# Tractive_System.net
KiCad netlist of a schematic drawn in EAGLE
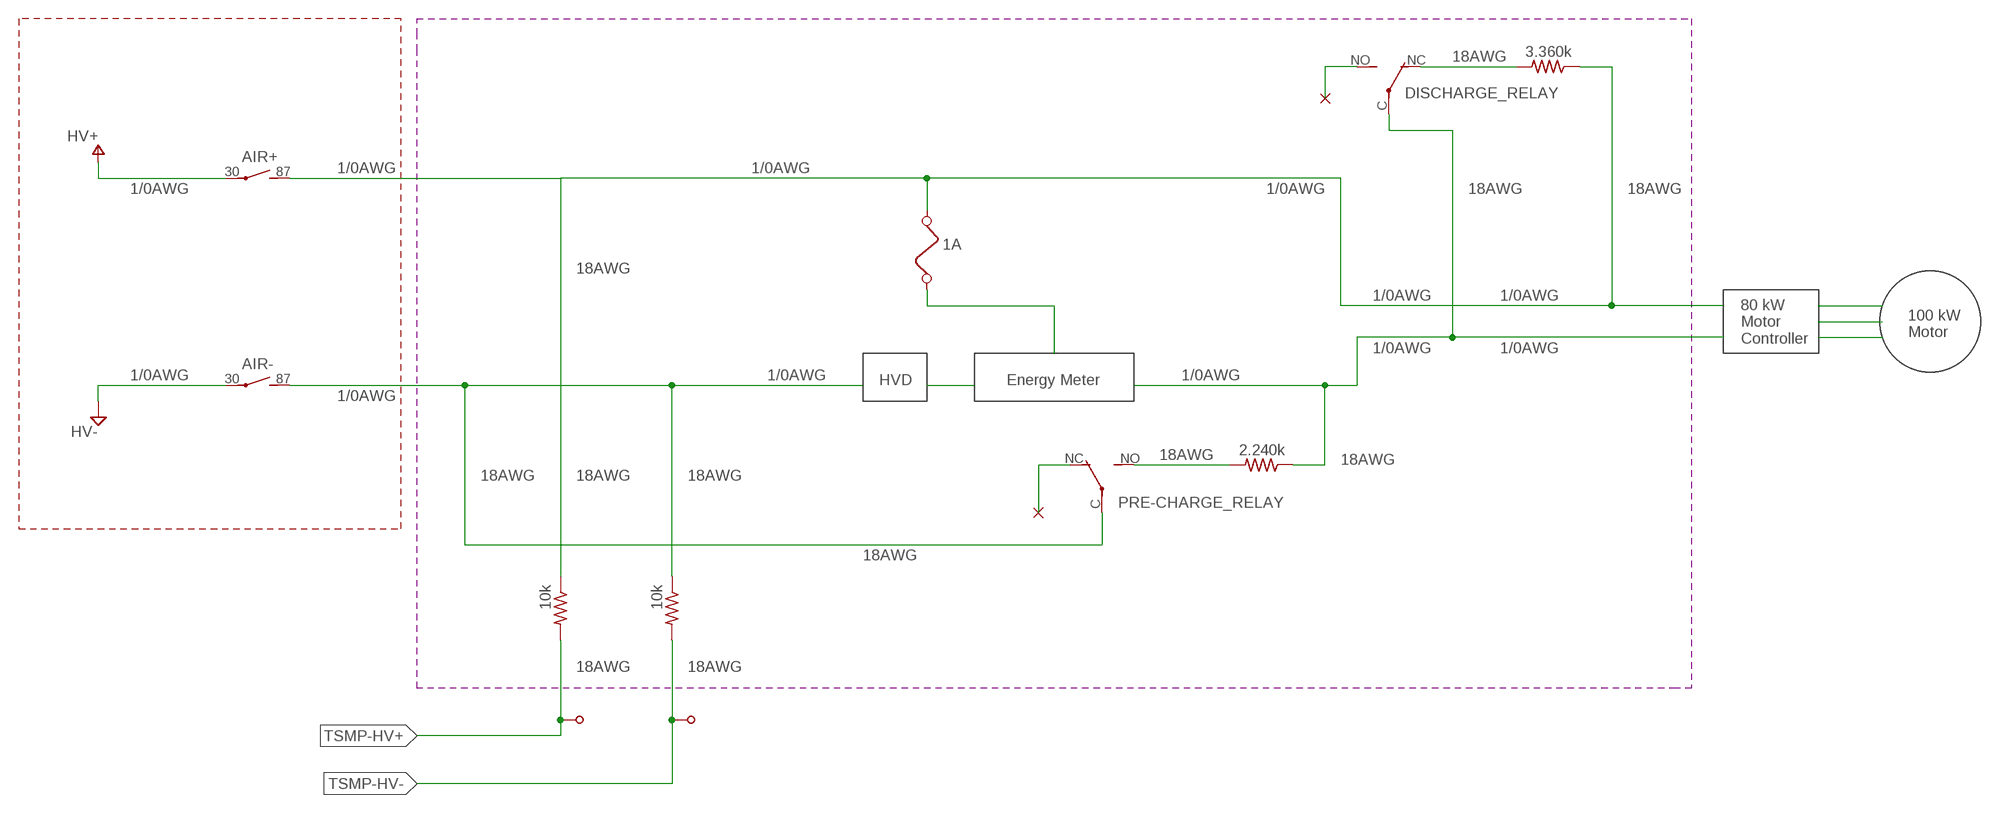
[diagram p0: schematic, sheet 1]

(export (version "E")
  (design (tool "Eeschema 10.0.6"))
  (components
    (comp (ref "AIR+")
      (value "CB1A-P-12V")
      (footprint "eagle-import:CB1")
      (fields (field (name "MF") "AROMAT/ MATSUSHITA"))
      (libsource (lib "eagle-import") (part "CB1A-P-12V"))
    )
    (comp (ref "AIR-")
      (value "CB1A-P-12V")
      (footprint "eagle-import:CB1")
      (fields (field (name "MF") "AROMAT/ MATSUSHITA"))
      (libsource (lib "eagle-import") (part "CB1A-P-12V"))
    )
    (comp (ref "DISCHARGE_RELAY")
      (value "CT112")
      (footprint "eagle-import:CT-SLIM")
      (libsource (lib "eagle-import") (part "CT112"))
    )
    (comp (ref "F1")
      (value "1A")
      (footprint "eagle-import:FUSE")
      (libsource (lib "eagle-import") (part "FUSE"))
    )
    (comp (ref "PRE-CHARGE_RELAY")
      (value "CT112")
      (footprint "eagle-import:CT-SLIM")
      (libsource (lib "eagle-import") (part "CT112"))
    )
    (comp (ref "R1")
      (value "3.360k")
      (footprint "eagle-import:R0805")
      (libsource (lib "eagle-import") (part "R-US_R0805"))
    )
    (comp (ref "R2")
      (value "10k")
      (footprint "eagle-import:R0805")
      (libsource (lib "eagle-import") (part "R-US_R0805"))
    )
    (comp (ref "R3")
      (value "2.240k")
      (footprint "eagle-import:R0805")
      (libsource (lib "eagle-import") (part "R-US_R0805"))
    )
    (comp (ref "R4")
      (value "10k")
      (footprint "eagle-import:R0805")
      (libsource (lib "eagle-import") (part "R-US_R0805"))
    )
    (comp (ref "U$1")
      (value "BANANA-JACK")
      (footprint "eagle-import:BANANA-PRINT")
      (libsource (lib "eagle-import") (part "BANANA-JACK"))
    )
    (comp (ref "U$3")
      (value "BANANA-JACK")
      (footprint "eagle-import:BANANA-PRINT")
      (libsource (lib "eagle-import") (part "BANANA-JACK"))
    )
  )
  (nets
    (net (code "1") (name "HV+") (class "Default")
      (node (ref "AIR+") (pin "30") (pinfunction "P_30") (pintype "passive"))
    )
    (net (code "2") (name "HV-") (class "Default")
      (node (ref "AIR-") (pin "30") (pinfunction "P_30") (pintype "passive"))
    )
    (net (code "3") (name "Net-(AIR+B-S)") (class "Default")
      (node (ref "AIR+") (pin "87") (pinfunction "S_87") (pintype "passive"))
      (node (ref "F1") (pin "2") (pinfunction "2_2") (pintype "passive"))
      (node (ref "R1") (pin "1") (pinfunction "1_1") (pintype "passive"))
      (node (ref "R2") (pin "1") (pinfunction "1_1") (pintype "passive"))
    )
    (net (code "4") (name "Net-(AIR-B-S)") (class "Default")
      (node (ref "AIR-") (pin "87") (pinfunction "S_87") (pintype "passive"))
      (node (ref "PRE-CHARGE_RELAY") (pin "C") (pinfunction "P_C") (pintype "passive"))
      (node (ref "R4") (pin "1") (pinfunction "1_1") (pintype "passive"))
    )
    (net (code "5") (name "Net-(DISCHARGE_RELAYB-O)") (class "Default")
      (node (ref "DISCHARGE_RELAY") (pin "NC") (pinfunction "O_NC") (pintype "passive"))
      (node (ref "R1") (pin "2") (pinfunction "2_2") (pintype "passive"))
    )
    (net (code "6") (name "Net-(DISCHARGE_RELAYB-P)") (class "Default")
      (node (ref "DISCHARGE_RELAY") (pin "C") (pinfunction "P_C") (pintype "passive"))
      (node (ref "R3") (pin "1") (pinfunction "1_1") (pintype "passive"))
    )
    (net (code "7") (name "Net-(PRE-CHARGE_RELAYB-S)") (class "Default")
      (node (ref "PRE-CHARGE_RELAY") (pin "NO") (pinfunction "S_NO") (pintype "passive"))
      (node (ref "R3") (pin "2") (pinfunction "2_2") (pintype "passive"))
    )
    (net (code "8") (name "TSMP-HV+") (class "Default")
      (node (ref "R2") (pin "2") (pinfunction "2_2") (pintype "passive"))
      (node (ref "U$1") (pin "P$1") (pinfunction "PIN_P$1") (pintype "bidirectional"))
    )
    (net (code "9") (name "TSMP-HV-") (class "Default")
      (node (ref "R4") (pin "2") (pinfunction "2_2") (pintype "passive"))
      (node (ref "U$3") (pin "P$1") (pinfunction "PIN_P$1") (pintype "bidirectional"))
    )
    (net (code "10") (name "unconnected-(DISCHARGE_RELAYB-S-PadNO)") (class "Default")
      (node (ref "DISCHARGE_RELAY") (pin "NO") (pinfunction "S_NO") (pintype "passive"))
    )
    (net (code "11") (name "unconnected-(F1-Pad1)") (class "Default")
      (node (ref "F1") (pin "1") (pinfunction "1_1") (pintype "passive"))
    )
    (net (code "12") (name "unconnected-(PRE-CHARGE_RELAYB-O-PadNC)") (class "Default")
      (node (ref "PRE-CHARGE_RELAY") (pin "NC") (pinfunction "O_NC") (pintype "passive"))
    )
  )
)
